# SF354_adapter_pcb_v1_5.net
KiCad netlist of a schematic drawn in EAGLE
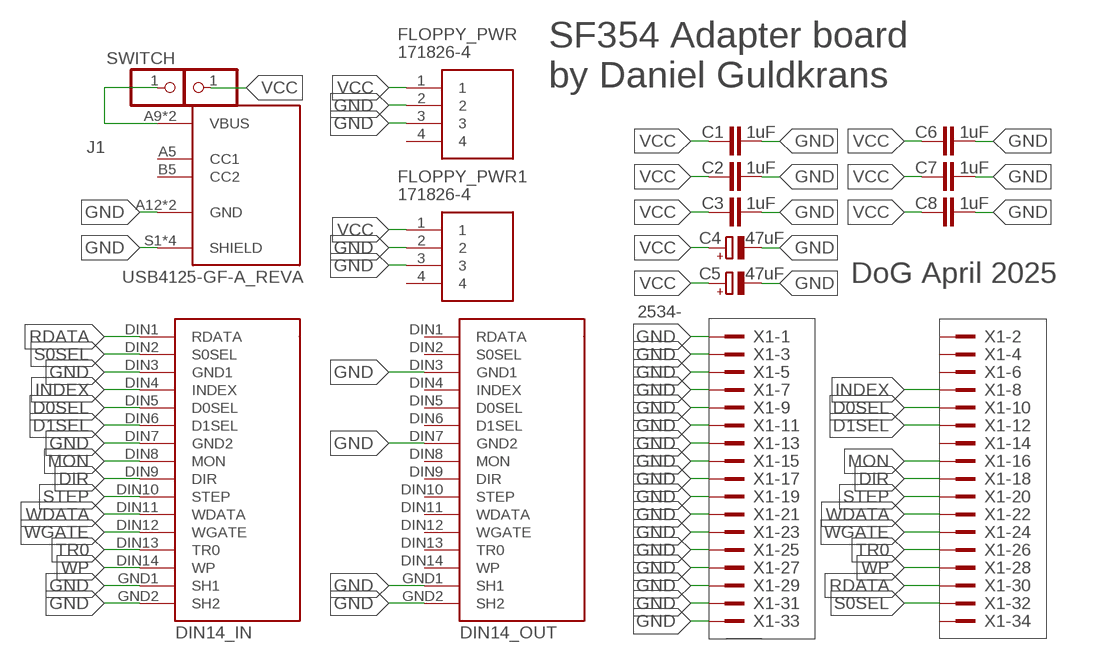
[diagram p0: schematic, sheet 1]

(export (version "E")
  (design (tool "Eeschema 10.0.6"))
  (components
    (comp (ref "C1")
      (value "1uF")
      (footprint "eagle-import:C1206")
      (libsource (lib "eagle-import") (part "C-EUC1206"))
    )
    (comp (ref "C2")
      (value "1uF")
      (footprint "eagle-import:C0805")
      (libsource (lib "eagle-import") (part "C-EUC0805"))
    )
    (comp (ref "C3")
      (value "1uF")
      (footprint "eagle-import:C050-025X075")
      (libsource (lib "eagle-import") (part "C-EU050-025X075"))
    )
    (comp (ref "C4")
      (value "47uF")
      (footprint "eagle-import:UD-6,3X7,7_NICHICON")
      (libsource (lib "eagle-import") (part "CPOL-EUUD-6,3X7,7"))
    )
    (comp (ref "C5")
      (value "47uF")
      (footprint "eagle-import:E5-10,5")
      (libsource (lib "eagle-import") (part "CPOL-EUE5-10.5"))
    )
    (comp (ref "C6")
      (value "1uF")
      (footprint "eagle-import:C1206")
      (libsource (lib "eagle-import") (part "C-EUC1206"))
    )
    (comp (ref "C7")
      (value "1uF")
      (footprint "eagle-import:C0805")
      (libsource (lib "eagle-import") (part "C-EUC0805"))
    )
    (comp (ref "C8")
      (value "1uF")
      (footprint "eagle-import:C050-025X075")
      (libsource (lib "eagle-import") (part "C-EU050-025X075"))
    )
    (comp (ref "FLOPPY_PWR")
      (value "171826-4")
      (footprint "eagle-import:SHDRRA4W69P0X250_1X4_1000X1350")
      (fields (field (name "MOUSER_PART_NUMBER") "571-1718264"))
      (libsource (lib "eagle-import") (part "171826-4"))
    )
    (comp (ref "FLOPPY_PWR1")
      (value "171826-4")
      (footprint "eagle-import:SHDRRA4W69P0X250_1X4_1000X1350")
      (fields (field (name "MOUSER_PART_NUMBER") "571-1718264"))
      (libsource (lib "eagle-import") (part "171826-4"))
    )
    (comp (ref "J1")
      (value "USB4125-GF-A_REVA")
      (footprint "eagle-import:GCT_USB4125-GF-A_REVA")
      (fields (field (name "MF") "Global Connector Technology") (field (name "MP") "USB4125-GF-A"))
      (libsource (lib "eagle-import") (part "USB4125-GF-A_REVA"))
    )
    (comp (ref "JP1")
      (value "PINHD-1X11X01_BH")
      (footprint "eagle-import:1X01_BH")
      (libsource (lib "eagle-import") (part "PINHD-1X11X01_BH"))
    )
    (comp (ref "JP2")
      (value "PINHD-1X11X01_BH")
      (footprint "eagle-import:1X01_BH")
      (libsource (lib "eagle-import") (part "PINHD-1X11X01_BH"))
    )
    (comp (ref "U$1")
      (value "DIN14")
      (footprint "eagle-import:DIN14")
      (libsource (lib "eagle-import") (part "DIN14"))
    )
    (comp (ref "U$2")
      (value "DIN14")
      (footprint "eagle-import:DIN14")
      (libsource (lib "eagle-import") (part "DIN14"))
    )
    (comp (ref "X1")
      (value "2534-")
      (footprint "eagle-import:PAK100_2500-34")
      (libsource (lib "eagle-import") (part "2534-"))
    )
  )
  (nets
    (net (code "1") (name "D0SEL") (class "Default")
      (node (ref "U$1") (pin "DIN5") (pinfunction "D0SEL_DIN5") (pintype "bidirectional"))
      (node (ref "X1") (pin "10") (pinfunction "KL_10") (pintype "passive"))
    )
    (net (code "2") (name "D1SEL") (class "Default")
      (node (ref "U$1") (pin "DIN6") (pinfunction "D1SEL_DIN6") (pintype "bidirectional"))
      (node (ref "X1") (pin "12") (pinfunction "KL_12") (pintype "passive"))
    )
    (net (code "3") (name "DIR") (class "Default")
      (node (ref "U$1") (pin "DIN9") (pinfunction "DIR_DIN9") (pintype "bidirectional"))
      (node (ref "X1") (pin "18") (pinfunction "KL_18") (pintype "passive"))
    )
    (net (code "4") (name "GND") (class "Default")
      (node (ref "C1") (pin "2") (pinfunction "2_2") (pintype "passive"))
      (node (ref "C2") (pin "2") (pinfunction "2_2") (pintype "passive"))
      (node (ref "C3") (pin "2") (pinfunction "2_2") (pintype "passive"))
      (node (ref "C4") (pin "-") (pinfunction "-_-") (pintype "passive"))
      (node (ref "C5") (pin "-") (pinfunction "-_-") (pintype "passive"))
      (node (ref "C6") (pin "2") (pinfunction "2_2") (pintype "passive"))
      (node (ref "C7") (pin "2") (pinfunction "2_2") (pintype "passive"))
      (node (ref "C8") (pin "2") (pinfunction "2_2") (pintype "passive"))
      (node (ref "FLOPPY_PWR") (pin "2") (pinfunction "2_2") (pintype "bidirectional"))
      (node (ref "FLOPPY_PWR") (pin "3") (pinfunction "3_3") (pintype "bidirectional"))
      (node (ref "FLOPPY_PWR1") (pin "2") (pinfunction "2_2") (pintype "bidirectional"))
      (node (ref "FLOPPY_PWR1") (pin "3") (pinfunction "3_3") (pintype "bidirectional"))
      (node (ref "J1") (pin "A12") (pinfunction "GND_A12") (pintype "power_in"))
      (node (ref "J1") (pin "B12") (pinfunction "GND_B12") (pintype "power_in"))
      (node (ref "J1") (pin "S1") (pinfunction "SHIELD_S1") (pintype "passive"))
      (node (ref "J1") (pin "S2") (pinfunction "SHIELD_S2") (pintype "passive"))
      (node (ref "J1") (pin "S3") (pinfunction "SHIELD_S3") (pintype "passive"))
      (node (ref "J1") (pin "S4") (pinfunction "SHIELD_S4") (pintype "passive"))
      (node (ref "U$1") (pin "DIN3") (pinfunction "GND1_DIN3") (pintype "bidirectional"))
      (node (ref "U$1") (pin "DIN7") (pinfunction "GND2_DIN7") (pintype "bidirectional"))
      (node (ref "U$1") (pin "GND1") (pinfunction "SH1_GND1") (pintype "bidirectional"))
      (node (ref "U$1") (pin "GND2") (pinfunction "SH2_GND2") (pintype "bidirectional"))
      (node (ref "U$2") (pin "DIN3") (pinfunction "GND1_DIN3") (pintype "bidirectional"))
      (node (ref "U$2") (pin "DIN7") (pinfunction "GND2_DIN7") (pintype "bidirectional"))
      (node (ref "U$2") (pin "GND1") (pinfunction "SH1_GND1") (pintype "bidirectional"))
      (node (ref "U$2") (pin "GND2") (pinfunction "SH2_GND2") (pintype "bidirectional"))
      (node (ref "X1") (pin "1") (pinfunction "KL_1") (pintype "passive"))
      (node (ref "X1") (pin "11") (pinfunction "KL_11") (pintype "passive"))
      (node (ref "X1") (pin "13") (pinfunction "KL_13") (pintype "passive"))
      (node (ref "X1") (pin "15") (pinfunction "KL_15") (pintype "passive"))
      (node (ref "X1") (pin "17") (pinfunction "KL_17") (pintype "passive"))
      (node (ref "X1") (pin "19") (pinfunction "KL_19") (pintype "passive"))
      (node (ref "X1") (pin "21") (pinfunction "KL_21") (pintype "passive"))
      (node (ref "X1") (pin "23") (pinfunction "KL_23") (pintype "passive"))
      (node (ref "X1") (pin "25") (pinfunction "KL_25") (pintype "passive"))
      (node (ref "X1") (pin "27") (pinfunction "KL_27") (pintype "passive"))
      (node (ref "X1") (pin "29") (pinfunction "KL_29") (pintype "passive"))
      (node (ref "X1") (pin "3") (pinfunction "KL_3") (pintype "passive"))
      (node (ref "X1") (pin "31") (pinfunction "KL_31") (pintype "passive"))
      (node (ref "X1") (pin "33") (pinfunction "KL_33") (pintype "passive"))
      (node (ref "X1") (pin "5") (pinfunction "KL_5") (pintype "passive"))
      (node (ref "X1") (pin "7") (pinfunction "KL_7") (pintype "passive"))
      (node (ref "X1") (pin "9") (pinfunction "KL_9") (pintype "passive"))
    )
    (net (code "5") (name "INDEX") (class "Default")
      (node (ref "U$1") (pin "DIN4") (pinfunction "INDEX_DIN4") (pintype "bidirectional"))
      (node (ref "X1") (pin "8") (pinfunction "KL_8") (pintype "passive"))
    )
    (net (code "6") (name "MON") (class "Default")
      (node (ref "U$1") (pin "DIN8") (pinfunction "MON_DIN8") (pintype "bidirectional"))
      (node (ref "X1") (pin "16") (pinfunction "KL_16") (pintype "passive"))
    )
    (net (code "7") (name "Net-(J1-VBUS-PadA9)") (class "Default")
      (node (ref "J1") (pin "A9") (pinfunction "VBUS_A9") (pintype "power_in"))
      (node (ref "J1") (pin "B9") (pinfunction "VBUS_B9") (pintype "power_in"))
      (node (ref "JP2") (pin "1") (pinfunction "1_1") (pintype "passive"))
    )
    (net (code "8") (name "RDATA") (class "Default")
      (node (ref "U$1") (pin "DIN1") (pinfunction "RDATA_DIN1") (pintype "bidirectional"))
      (node (ref "X1") (pin "30") (pinfunction "KL_30") (pintype "passive"))
    )
    (net (code "9") (name "S0SEL") (class "Default")
      (node (ref "U$1") (pin "DIN2") (pinfunction "S0SEL_DIN2") (pintype "bidirectional"))
      (node (ref "X1") (pin "32") (pinfunction "KL_32") (pintype "passive"))
    )
    (net (code "10") (name "STEP") (class "Default")
      (node (ref "U$1") (pin "DIN10") (pinfunction "STEP_DIN10") (pintype "bidirectional"))
      (node (ref "X1") (pin "20") (pinfunction "KL_20") (pintype "passive"))
    )
    (net (code "11") (name "TR0") (class "Default")
      (node (ref "U$1") (pin "DIN13") (pinfunction "TR0_DIN13") (pintype "bidirectional"))
      (node (ref "X1") (pin "26") (pinfunction "KL_26") (pintype "passive"))
    )
    (net (code "12") (name "VCC") (class "Default")
      (node (ref "C1") (pin "1") (pinfunction "1_1") (pintype "passive"))
      (node (ref "C2") (pin "1") (pinfunction "1_1") (pintype "passive"))
      (node (ref "C3") (pin "1") (pinfunction "1_1") (pintype "passive"))
      (node (ref "C4") (pin "+") (pinfunction "+_+") (pintype "passive"))
      (node (ref "C5") (pin "+") (pinfunction "+_+") (pintype "passive"))
      (node (ref "C6") (pin "1") (pinfunction "1_1") (pintype "passive"))
      (node (ref "C7") (pin "1") (pinfunction "1_1") (pintype "passive"))
      (node (ref "C8") (pin "1") (pinfunction "1_1") (pintype "passive"))
      (node (ref "FLOPPY_PWR") (pin "1") (pinfunction "1_1") (pintype "bidirectional"))
      (node (ref "FLOPPY_PWR1") (pin "1") (pinfunction "1_1") (pintype "bidirectional"))
      (node (ref "JP1") (pin "1") (pinfunction "1_1") (pintype "passive"))
    )
    (net (code "13") (name "WDATA") (class "Default")
      (node (ref "U$1") (pin "DIN11") (pinfunction "WDATA_DIN11") (pintype "bidirectional"))
      (node (ref "X1") (pin "22") (pinfunction "KL_22") (pintype "passive"))
    )
    (net (code "14") (name "WGATE") (class "Default")
      (node (ref "U$1") (pin "DIN12") (pinfunction "WGATE_DIN12") (pintype "bidirectional"))
      (node (ref "X1") (pin "24") (pinfunction "KL_24") (pintype "passive"))
    )
    (net (code "15") (name "WP") (class "Default")
      (node (ref "U$1") (pin "DIN14") (pinfunction "WP_DIN14") (pintype "bidirectional"))
      (node (ref "X1") (pin "28") (pinfunction "KL_28") (pintype "passive"))
    )
    (net (code "16") (name "unconnected-(FLOPPY_PWR-Pad4)") (class "Default")
      (node (ref "FLOPPY_PWR") (pin "4") (pinfunction "4_4") (pintype "bidirectional"))
    )
    (net (code "17") (name "unconnected-(FLOPPY_PWR1-Pad4)") (class "Default")
      (node (ref "FLOPPY_PWR1") (pin "4") (pinfunction "4_4") (pintype "bidirectional"))
    )
    (net (code "18") (name "unconnected-(J1-CC1-PadA5)") (class "Default")
      (node (ref "J1") (pin "A5") (pinfunction "CC1_A5") (pintype "bidirectional"))
    )
    (net (code "19") (name "unconnected-(J1-CC2-PadB5)") (class "Default")
      (node (ref "J1") (pin "B5") (pinfunction "CC2_B5") (pintype "bidirectional"))
    )
    (net (code "20") (name "unconnected-(U$2-D0SEL-PadDIN5)") (class "Default")
      (node (ref "U$2") (pin "DIN5") (pinfunction "D0SEL_DIN5") (pintype "bidirectional"))
    )
    (net (code "21") (name "unconnected-(U$2-D1SEL-PadDIN6)") (class "Default")
      (node (ref "U$2") (pin "DIN6") (pinfunction "D1SEL_DIN6") (pintype "bidirectional"))
    )
    (net (code "22") (name "unconnected-(U$2-DIR-PadDIN9)") (class "Default")
      (node (ref "U$2") (pin "DIN9") (pinfunction "DIR_DIN9") (pintype "bidirectional"))
    )
    (net (code "23") (name "unconnected-(U$2-INDEX-PadDIN4)") (class "Default")
      (node (ref "U$2") (pin "DIN4") (pinfunction "INDEX_DIN4") (pintype "bidirectional"))
    )
    (net (code "24") (name "unconnected-(U$2-MON-PadDIN8)") (class "Default")
      (node (ref "U$2") (pin "DIN8") (pinfunction "MON_DIN8") (pintype "bidirectional"))
    )
    (net (code "25") (name "unconnected-(U$2-RDATA-PadDIN1)") (class "Default")
      (node (ref "U$2") (pin "DIN1") (pinfunction "RDATA_DIN1") (pintype "bidirectional"))
    )
    (net (code "26") (name "unconnected-(U$2-S0SEL-PadDIN2)") (class "Default")
      (node (ref "U$2") (pin "DIN2") (pinfunction "S0SEL_DIN2") (pintype "bidirectional"))
    )
    (net (code "27") (name "unconnected-(U$2-STEP-PadDIN10)") (class "Default")
      (node (ref "U$2") (pin "DIN10") (pinfunction "STEP_DIN10") (pintype "bidirectional"))
    )
    (net (code "28") (name "unconnected-(U$2-TR0-PadDIN13)") (class "Default")
      (node (ref "U$2") (pin "DIN13") (pinfunction "TR0_DIN13") (pintype "bidirectional"))
    )
    (net (code "29") (name "unconnected-(U$2-WDATA-PadDIN11)") (class "Default")
      (node (ref "U$2") (pin "DIN11") (pinfunction "WDATA_DIN11") (pintype "bidirectional"))
    )
    (net (code "30") (name "unconnected-(U$2-WGATE-PadDIN12)") (class "Default")
      (node (ref "U$2") (pin "DIN12") (pinfunction "WGATE_DIN12") (pintype "bidirectional"))
    )
    (net (code "31") (name "unconnected-(U$2-WP-PadDIN14)") (class "Default")
      (node (ref "U$2") (pin "DIN14") (pinfunction "WP_DIN14") (pintype "bidirectional"))
    )
    (net (code "32") (name "unconnected-(X1AB-KL-Pad34)") (class "Default")
      (node (ref "X1") (pin "34") (pinfunction "KL_34") (pintype "passive"))
    )
    (net (code "33") (name "unconnected-(X1AC-KL-Pad4)") (class "Default")
      (node (ref "X1") (pin "4") (pinfunction "KL_4") (pintype "passive"))
    )
    (net (code "34") (name "unconnected-(X1AE-KL-Pad6)") (class "Default")
      (node (ref "X1") (pin "6") (pinfunction "KL_6") (pintype "passive"))
    )
    (net (code "35") (name "unconnected-(X1F-KL-Pad14)") (class "Default")
      (node (ref "X1") (pin "14") (pinfunction "KL_14") (pintype "passive"))
    )
    (net (code "36") (name "unconnected-(X1L-KL-Pad2)") (class "Default")
      (node (ref "X1") (pin "2") (pinfunction "KL_2") (pintype "passive"))
    )
  )
)
